# 2_ADC.net
KiCad netlist of a schematic drawn in Altium Designer
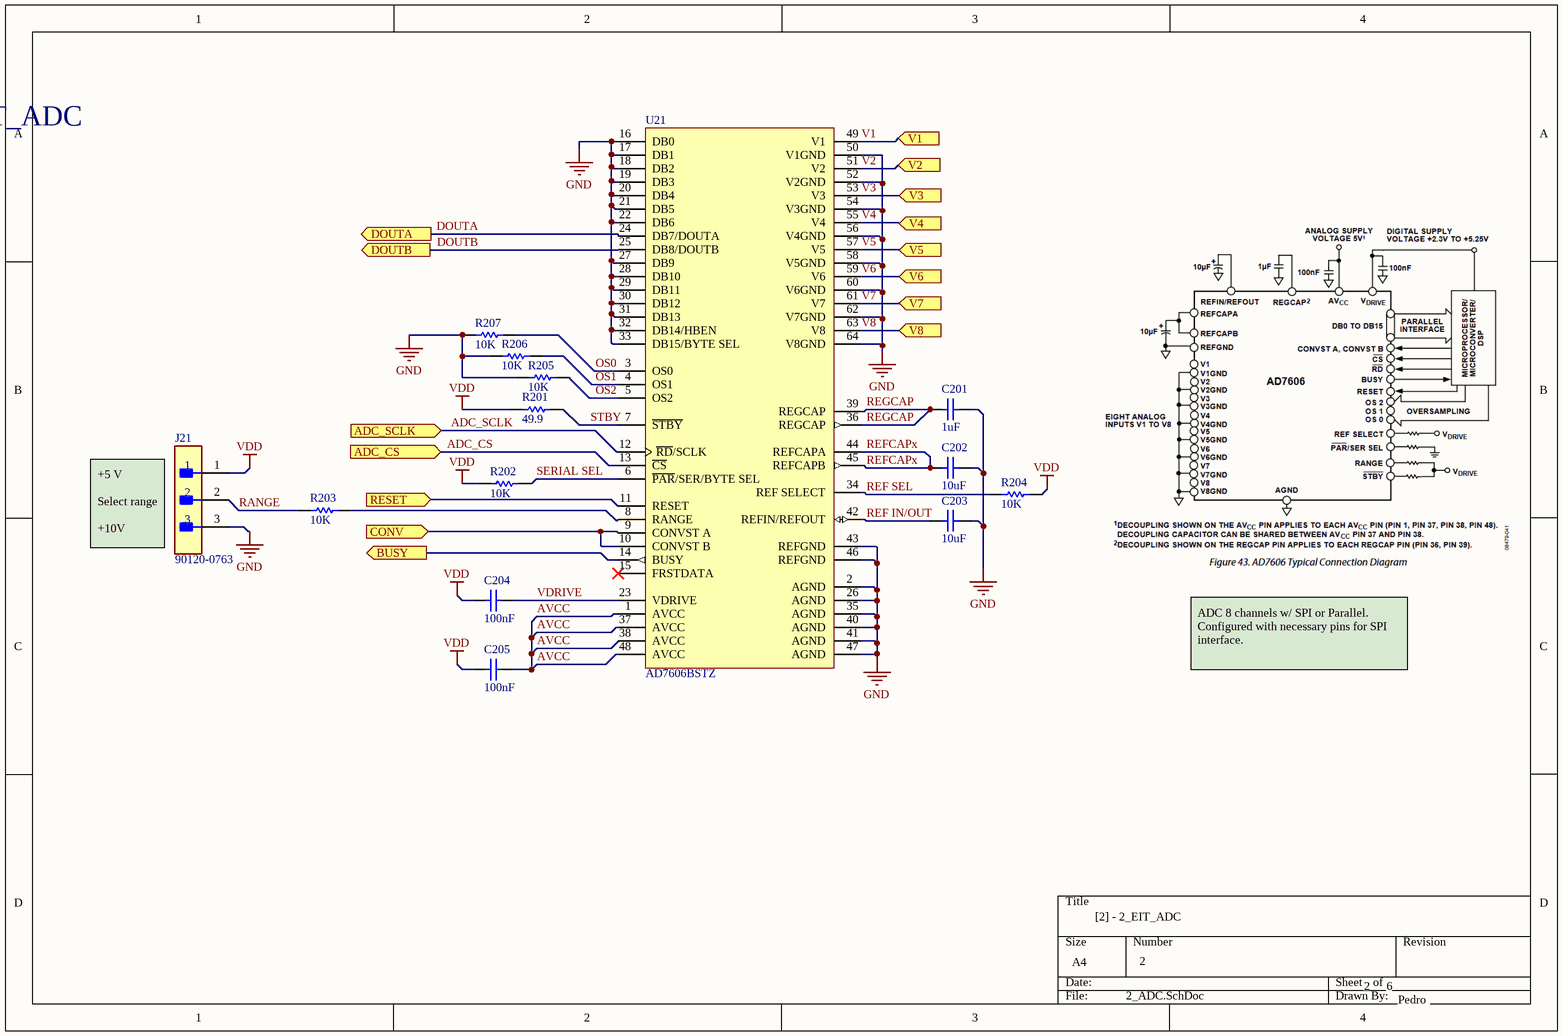
[diagram p0: 2_ADC.SchDoc]

(export (version "E")
  (design (tool "Eeschema 10.0.6"))
  (components
    (comp (ref "C201")
      (value "1uF")
      (footprint "CAPC1005X55X30LL05T10")
      (description "generic")
      (libsource (lib "RPI_EIT_SchLib") (part "Capacitor"))
    )
    (comp (ref "C202")
      (value "10uF")
      (footprint "FP-C0603C-CF-IPC_A")
      (description "generic")
      (libsource (lib "RPI_EIT_SchLib") (part "Capacitor"))
    )
    (comp (ref "C203")
      (value "10uF")
      (footprint "FP-C0603C-CF-IPC_A")
      (description "generic")
      (libsource (lib "RPI_EIT_SchLib") (part "Capacitor"))
    )
    (comp (ref "C204")
      (value "100nF")
      (footprint "CAPC1005X55X30LL05T10")
      (description "generic")
      (libsource (lib "RPI_EIT_SchLib") (part "Capacitor"))
    )
    (comp (ref "C205")
      (value "100nF")
      (footprint "CAPC1005X55X30LL05T10")
      (description "generic")
      (libsource (lib "RPI_EIT_SchLib") (part "Capacitor"))
    )
    (comp (ref "J21")
      (value "90120-0763")
      (footprint "FP-90120-0763-MFG")
      (description "CONN HEADER VERT 3POS 2.54MM")
      (fields
        (field (name "MANUFACTURER") "Molex")
        (field (name "OCTOPART") "https://octopart.com/90120-0763-molex-655433")
      )
      (libsource (lib "Altium Content Vault") (part "0d3f023dd272f625e17a2be33dea85f"))
    )
    (comp (ref "R201")
      (value "RC0603JR-070RL")
      (footprint "RESC1608X55X25LL10T15")
      (description "Chip Resistor, 0 Ohm, +/- 5%, 0.1 W, -55 to 155 degC, 0603 (1608 Metric), RoHS, Tape and Reel")
      (fields
        (field (name "TOLERANCE") "5%")
        (field (name "RESISTANCE") "49.9")
        (field (name "MANUFACTURER") "Yageo")
      )
      (libsource (lib "RPI_EIT_SchLib") (part "RES-2"))
    )
    (comp (ref "R202")
      (value "RC0603JR-070RL")
      (footprint "RESC1608X55X25LL10T15")
      (description "Chip Resistor, 0 Ohm, +/- 5%, 0.1 W, -55 to 155 degC, 0603 (1608 Metric), RoHS, Tape and Reel")
      (fields
        (field (name "TOLERANCE") "5%")
        (field (name "RESISTANCE") "10K")
        (field (name "MANUFACTURER") "Yageo")
      )
      (libsource (lib "RPI_EIT_SchLib") (part "RES-2"))
    )
    (comp (ref "R203")
      (value "RC0603JR-070RL")
      (footprint "RESC1608X55X25LL10T15")
      (description "Chip Resistor, 0 Ohm, +/- 5%, 0.1 W, -55 to 155 degC, 0603 (1608 Metric), RoHS, Tape and Reel")
      (fields
        (field (name "TOLERANCE") "5%")
        (field (name "RESISTANCE") "10K")
        (field (name "MANUFACTURER") "Yageo")
      )
      (libsource (lib "RPI_EIT_SchLib") (part "RES-2"))
    )
    (comp (ref "R204")
      (value "RC0603JR-070RL")
      (footprint "RESC1608X55X25LL10T15")
      (description "Chip Resistor, 0 Ohm, +/- 5%, 0.1 W, -55 to 155 degC, 0603 (1608 Metric), RoHS, Tape and Reel")
      (fields
        (field (name "TOLERANCE") "5%")
        (field (name "RESISTANCE") "10K")
        (field (name "MANUFACTURER") "Yageo")
      )
      (libsource (lib "RPI_EIT_SchLib") (part "RES-2"))
    )
    (comp (ref "R205")
      (value "RC0603JR-070RL")
      (footprint "RESC1608X55X25LL10T15")
      (description "Chip Resistor, 0 Ohm, +/- 5%, 0.1 W, -55 to 155 degC, 0603 (1608 Metric), RoHS, Tape and Reel")
      (fields
        (field (name "TOLERANCE") "5%")
        (field (name "RESISTANCE") "10K")
        (field (name "MANUFACTURER") "Yageo")
      )
      (libsource (lib "RPI_EIT_SchLib") (part "RES-2"))
    )
    (comp (ref "R206")
      (value "RC0603JR-070RL")
      (footprint "RESC1608X55X25LL10T15")
      (description "Chip Resistor, 0 Ohm, +/- 5%, 0.1 W, -55 to 155 degC, 0603 (1608 Metric), RoHS, Tape and Reel")
      (fields
        (field (name "TOLERANCE") "5%")
        (field (name "RESISTANCE") "10K")
        (field (name "MANUFACTURER") "Yageo")
      )
      (libsource (lib "RPI_EIT_SchLib") (part "RES-2"))
    )
    (comp (ref "R207")
      (value "RC0603JR-070RL")
      (footprint "RESC1608X55X25LL10T15")
      (description "Chip Resistor, 0 Ohm, +/- 5%, 0.1 W, -55 to 155 degC, 0603 (1608 Metric), RoHS, Tape and Reel")
      (fields
        (field (name "TOLERANCE") "5%")
        (field (name "RESISTANCE") "10K")
        (field (name "MANUFACTURER") "Yageo")
      )
      (libsource (lib "RPI_EIT_SchLib") (part "RES-2"))
    )
    (comp (ref "U21")
      (value "AD7606BSTZ")
      (footprint "ST-64-2_L")
      (fields (field (name "GENERIC PART NUMBER") "AD7606") (field (name "MANUFACTURER") "Analog Devices"))
      (libsource (lib "Altium Content Vault") (part "ADI-AD7606-ST-64-2"))
    )
  )
  (nets
    (net (code "1") (name "/ADC_CS") (class "Default")
      (node (ref "U21") (pin "13") (pinfunction "~{CS}_13") (pintype "passive"))
    )
    (net (code "2") (name "/ADC_SCLK") (class "Default")
      (node (ref "U21") (pin "12") (pinfunction "~{RD}/SCLK_12") (pintype "passive"))
    )
    (net (code "3") (name "/AVCC") (class "Default")
      (node (ref "C205") (pin "1") (pinfunction "1_1") (pintype "passive"))
      (node (ref "U21") (pin "1") (pinfunction "AVCC_1") (pintype "power_in"))
      (node (ref "U21") (pin "37") (pinfunction "AVCC_37") (pintype "power_in"))
      (node (ref "U21") (pin "38") (pinfunction "AVCC_38") (pintype "power_in"))
      (node (ref "U21") (pin "48") (pinfunction "AVCC_48") (pintype "power_in"))
    )
    (net (code "4") (name "/BUSY") (class "Default")
      (node (ref "U21") (pin "14") (pinfunction "BUSY_14") (pintype "output"))
    )
    (net (code "5") (name "/CONV") (class "Default")
      (node (ref "U21") (pin "10") (pinfunction "CONVST_B_10") (pintype "passive"))
      (node (ref "U21") (pin "9") (pinfunction "CONVST_A_9") (pintype "passive"))
    )
    (net (code "6") (name "/DOUTA") (class "Default")
      (node (ref "U21") (pin "24") (pinfunction "DB7/DOUTA_24") (pintype "passive"))
    )
    (net (code "7") (name "/DOUTB") (class "Default")
      (node (ref "U21") (pin "25") (pinfunction "DB8/DOUTB_25") (pintype "passive"))
    )
    (net (code "8") (name "/OS0") (class "Default")
      (node (ref "R207") (pin "1") (pinfunction "1_1") (pintype "passive"))
      (node (ref "U21") (pin "3") (pinfunction "OS0_3") (pintype "passive"))
    )
    (net (code "9") (name "/OS1") (class "Default")
      (node (ref "R206") (pin "1") (pinfunction "1_1") (pintype "passive"))
      (node (ref "U21") (pin "4") (pinfunction "OS1_4") (pintype "passive"))
    )
    (net (code "10") (name "/OS2") (class "Default")
      (node (ref "R205") (pin "1") (pinfunction "1_1") (pintype "passive"))
      (node (ref "U21") (pin "5") (pinfunction "OS2_5") (pintype "passive"))
    )
    (net (code "11") (name "/RANGE") (class "Default")
      (node (ref "J21") (pin "2") (pinfunction "2_2") (pintype "passive"))
      (node (ref "R203") (pin "2") (pinfunction "2_2") (pintype "passive"))
    )
    (net (code "12") (name "/REF IN{slash}OUT") (class "Default")
      (node (ref "C203") (pin "2") (pinfunction "2_2") (pintype "passive"))
      (node (ref "U21") (pin "42") (pinfunction "REFIN/REFOUT_42") (pintype "bidirectional"))
    )
    (net (code "13") (name "/REF SEL") (class "Default")
      (node (ref "R204") (pin "2") (pinfunction "2_2") (pintype "passive"))
      (node (ref "U21") (pin "34") (pinfunction "REF_SELECT_34") (pintype "passive"))
    )
    (net (code "14") (name "/REFCAPx") (class "Default")
      (node (ref "C202") (pin "2") (pinfunction "2_2") (pintype "passive"))
      (node (ref "U21") (pin "44") (pinfunction "REFCAPA_44") (pintype "passive"))
      (node (ref "U21") (pin "45") (pinfunction "REFCAPB_45") (pintype "output"))
    )
    (net (code "15") (name "/REGCAP") (class "Default")
      (node (ref "C201") (pin "2") (pinfunction "2_2") (pintype "passive"))
      (node (ref "U21") (pin "36") (pinfunction "REGCAP_36") (pintype "output"))
      (node (ref "U21") (pin "39") (pinfunction "REGCAP_39") (pintype "passive"))
    )
    (net (code "16") (name "/RESET") (class "Default")
      (node (ref "U21") (pin "11") (pinfunction "RESET_11") (pintype "passive"))
    )
    (net (code "17") (name "/SERIAL SEL") (class "Default")
      (node (ref "R202") (pin "1") (pinfunction "1_1") (pintype "passive"))
      (node (ref "U21") (pin "6") (pinfunction "~{PAR}/SER/BYTE_SEL_6") (pintype "passive"))
    )
    (net (code "18") (name "/STBY") (class "Default")
      (node (ref "R201") (pin "1") (pinfunction "1_1") (pintype "passive"))
      (node (ref "U21") (pin "7") (pinfunction "~{STBY}_7") (pintype "passive"))
    )
    (net (code "19") (name "/V1") (class "Default")
      (node (ref "U21") (pin "49") (pinfunction "V1_49") (pintype "passive"))
    )
    (net (code "20") (name "/V2") (class "Default")
      (node (ref "U21") (pin "51") (pinfunction "V2_51") (pintype "passive"))
    )
    (net (code "21") (name "/V3") (class "Default")
      (node (ref "U21") (pin "53") (pinfunction "V3_53") (pintype "passive"))
    )
    (net (code "22") (name "/V4") (class "Default")
      (node (ref "U21") (pin "55") (pinfunction "V4_55") (pintype "passive"))
    )
    (net (code "23") (name "/V5") (class "Default")
      (node (ref "U21") (pin "57") (pinfunction "V5_57") (pintype "passive"))
    )
    (net (code "24") (name "/V6") (class "Default")
      (node (ref "U21") (pin "59") (pinfunction "V6_59") (pintype "passive"))
    )
    (net (code "25") (name "/V7") (class "Default")
      (node (ref "U21") (pin "61") (pinfunction "V7_61") (pintype "passive"))
    )
    (net (code "26") (name "/V8") (class "Default")
      (node (ref "U21") (pin "63") (pinfunction "V8_63") (pintype "passive"))
    )
    (net (code "27") (name "/VDRIVE") (class "Default")
      (node (ref "C204") (pin "1") (pinfunction "1_1") (pintype "passive"))
      (node (ref "U21") (pin "23") (pinfunction "VDRIVE_23") (pintype "power_in"))
    )
    (net (code "28") (name "GND") (class "Default")
      (node (ref "C201") (pin "1") (pinfunction "1_1") (pintype "passive"))
      (node (ref "C202") (pin "1") (pinfunction "1_1") (pintype "passive"))
      (node (ref "C203") (pin "1") (pinfunction "1_1") (pintype "passive"))
      (node (ref "J21") (pin "3") (pinfunction "3_3") (pintype "passive"))
      (node (ref "R205") (pin "2") (pinfunction "2_2") (pintype "passive"))
      (node (ref "R206") (pin "2") (pinfunction "2_2") (pintype "passive"))
      (node (ref "R207") (pin "2") (pinfunction "2_2") (pintype "passive"))
      (node (ref "U21") (pin "16") (pinfunction "DB0_16") (pintype "passive"))
      (node (ref "U21") (pin "17") (pinfunction "DB1_17") (pintype "passive"))
      (node (ref "U21") (pin "18") (pinfunction "DB2_18") (pintype "passive"))
      (node (ref "U21") (pin "19") (pinfunction "DB3_19") (pintype "passive"))
      (node (ref "U21") (pin "2") (pinfunction "AGND_2") (pintype "power_in"))
      (node (ref "U21") (pin "20") (pinfunction "DB4_20") (pintype "passive"))
      (node (ref "U21") (pin "21") (pinfunction "DB5_21") (pintype "passive"))
      (node (ref "U21") (pin "22") (pinfunction "DB6_22") (pintype "passive"))
      (node (ref "U21") (pin "26") (pinfunction "AGND_26") (pintype "power_in"))
      (node (ref "U21") (pin "27") (pinfunction "DB9_27") (pintype "passive"))
      (node (ref "U21") (pin "28") (pinfunction "DB10_28") (pintype "passive"))
      (node (ref "U21") (pin "29") (pinfunction "DB11_29") (pintype "passive"))
      (node (ref "U21") (pin "30") (pinfunction "DB12_30") (pintype "passive"))
      (node (ref "U21") (pin "31") (pinfunction "DB13_31") (pintype "passive"))
      (node (ref "U21") (pin "32") (pinfunction "DB14/HBEN_32") (pintype "passive"))
      (node (ref "U21") (pin "33") (pinfunction "DB15/BYTE_SEL_33") (pintype "passive"))
      (node (ref "U21") (pin "35") (pinfunction "AGND_35") (pintype "power_in"))
      (node (ref "U21") (pin "40") (pinfunction "AGND_40") (pintype "power_in"))
      (node (ref "U21") (pin "41") (pinfunction "AGND_41") (pintype "power_in"))
      (node (ref "U21") (pin "43") (pinfunction "REFGND_43") (pintype "power_in"))
      (node (ref "U21") (pin "46") (pinfunction "REFGND_46") (pintype "power_in"))
      (node (ref "U21") (pin "47") (pinfunction "AGND_47") (pintype "power_in"))
      (node (ref "U21") (pin "50") (pinfunction "V1GND_50") (pintype "power_in"))
      (node (ref "U21") (pin "52") (pinfunction "V2GND_52") (pintype "power_in"))
      (node (ref "U21") (pin "54") (pinfunction "V3GND_54") (pintype "power_in"))
      (node (ref "U21") (pin "56") (pinfunction "V4GND_56") (pintype "power_in"))
      (node (ref "U21") (pin "58") (pinfunction "V5GND_58") (pintype "power_in"))
      (node (ref "U21") (pin "60") (pinfunction "V6GND_60") (pintype "power_in"))
      (node (ref "U21") (pin "62") (pinfunction "V7GND_62") (pintype "power_in"))
      (node (ref "U21") (pin "64") (pinfunction "V8GND_64") (pintype "power_in"))
    )
    (net (code "29") (name "Net-(U21-RANGE)") (class "Default")
      (node (ref "R203") (pin "1") (pinfunction "1_1") (pintype "passive"))
      (node (ref "U21") (pin "8") (pinfunction "RANGE_8") (pintype "passive"))
    )
    (net (code "30") (name "VDD") (class "Default")
      (node (ref "C204") (pin "2") (pinfunction "2_2") (pintype "passive"))
      (node (ref "C205") (pin "2") (pinfunction "2_2") (pintype "passive"))
      (node (ref "J21") (pin "1") (pinfunction "1_1") (pintype "passive"))
      (node (ref "R201") (pin "2") (pinfunction "2_2") (pintype "passive"))
      (node (ref "R202") (pin "2") (pinfunction "2_2") (pintype "passive"))
      (node (ref "R204") (pin "1") (pinfunction "1_1") (pintype "passive"))
    )
    (net (code "31") (name "unconnected-(U21-FRSTDATA-Pad15)") (class "Default")
      (node (ref "U21") (pin "15") (pinfunction "FRSTDATA_15") (pintype "tri_state+no_connect"))
    )
  )
)
